# Connectors.net
KiCad netlist of a schematic drawn in Altium Designer
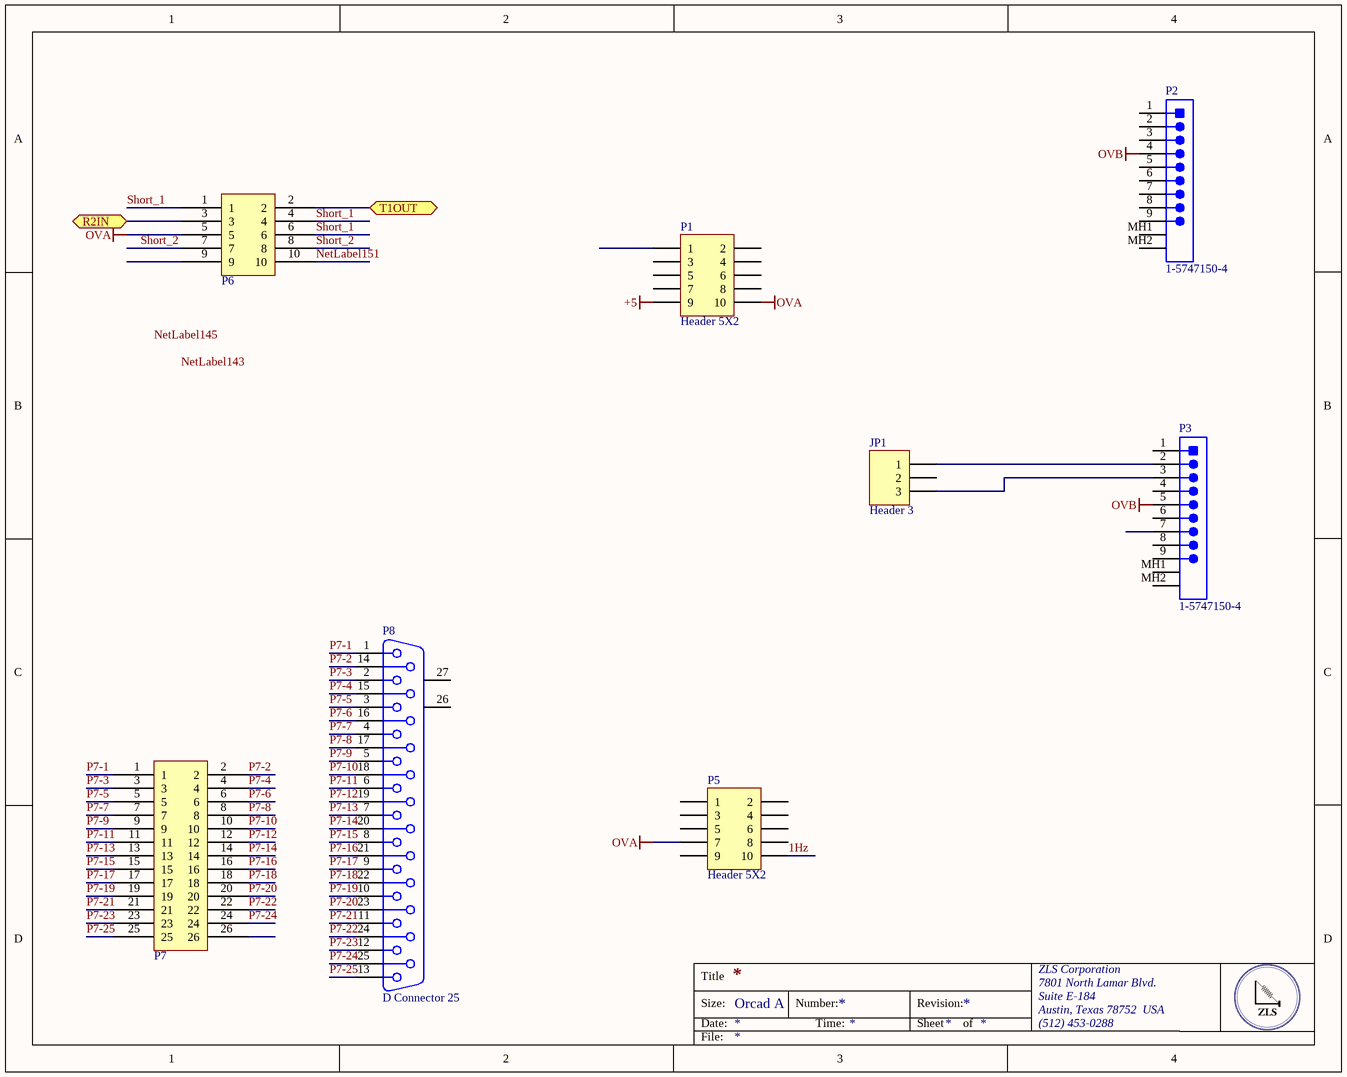
[diagram p0: Connectors.SchDoc]

(export (version "E")
  (design (tool "Eeschema 10.0.6"))
  (components
    (comp (ref "JP1")
      (value "Header 3")
      (footprint "HDR1X3")
      (description "Header, 3-Pin")
      (fields (field (name "PUBLISHER") "Altium Limited"))
      (libsource (lib "Miscellaneous Connectors") (part "Header 3"))
    )
    (comp (ref "P1")
      (value "Header 5X2")
      (footprint "HDR2X5")
      (description "Header, 5-Pin, Dual row")
      (fields (field (name "PUBLISHER") "Altium Limited"))
      (libsource (lib "Miscellaneous Connectors") (part "Header 5X2"))
    )
    (comp (ref "P2")
      (value "1-5747150-4")
      (footprint "TECO-1-5747150-4_V")
      (fields (field (name "MANUFACTURER") "TE Connectivity"))
      (libsource (lib "Altium Content Vault") (part "CMP-2000-05406-1"))
    )
    (comp (ref "P3")
      (value "1-5747150-4")
      (footprint "TECO-1-5747150-4_V")
      (fields (field (name "MANUFACTURER") "TE Connectivity"))
      (libsource (lib "Altium Content Vault") (part "CMP-2000-05406-1"))
    )
    (comp (ref "P5")
      (value "Header 5X2")
      (footprint "HDR2X5")
      (description "Header, 5-Pin, Dual row")
      (fields (field (name "PUBLISHER") "Altium Limited"))
      (libsource (lib "Miscellaneous Connectors") (part "Header 5X2"))
    )
    (comp (ref "P6")
      (value "STMM-105-01-G-D")
      (footprint "STMM-105-01-G-D")
      (fields
        (field (name "MANUFACTURER") "SAMTEC")
        (field (name "COMPONENTLINK1URL") "https://webassistants.partcommunity.com/23d-libs/samtec/search/resolve.html?EMAIL=mysamtec@samtec.com&PN=HTSW-114-05-F-D")
        (field (name "COMPONENTLINK1DESCRIPTION") "https://webassistants.partcommunity.com/23d-libs/samtec/search/resolve.html?EMAIL=mysamtec@samtec.com&PN=HTSW-114-05-F-D")
      )
      (libsource (lib "ZLS_Schematic_lib") (part "STMM-105-01-G-D"))
    )
    (comp (ref "P7")
      (value "2.00 mm Shrouded Terminal Strip, Cable Mate")
      (footprint "STMM-113-01-G-D")
      (libsource (lib "ZLS_Schematic_lib") (part "STMM-113-01-G-D"))
    )
    (comp (ref "P8")
      (value "D Connector 25")
      (footprint "DSUB1.385-2H25A")
      (description "Receptacle Assembly, 25 Position, Right Angle")
      (fields (field (name "PUBLISHER") "Altium Limited"))
      (libsource (lib "Miscellaneous Connectors") (part "D Connector 25"))
    )
  )
  (nets
    (net (code "1") (name "+5") (class "Default")
      (node (ref "P1") (pin "9") (pinfunction "9_9") (pintype "passive"))
    )
    (net (code "2") (name "/1Hz") (class "Default")
      (node (ref "P5") (pin "10") (pinfunction "10_10") (pintype "passive"))
    )
    (net (code "5") (name "/NetLabel151") (class "Default")
      (node (ref "P6") (pin "10") (pinfunction "10_10") (pintype "passive"))
    )
    (net (code "6") (name "/P7-1") (class "Default")
      (node (ref "P7") (pin "1") (pinfunction "1_1") (pintype "passive"))
      (node (ref "P8") (pin "1") (pinfunction "1_1") (pintype "passive"))
    )
    (net (code "7") (name "/P7-2") (class "Default")
      (node (ref "P7") (pin "2") (pinfunction "2_2") (pintype "passive"))
      (node (ref "P8") (pin "14") (pinfunction "14_14") (pintype "passive"))
    )
    (net (code "8") (name "/P7-3") (class "Default")
      (node (ref "P7") (pin "3") (pinfunction "3_3") (pintype "passive"))
      (node (ref "P8") (pin "2") (pinfunction "2_2") (pintype "passive"))
    )
    (net (code "9") (name "/P7-4") (class "Default")
      (node (ref "P7") (pin "4") (pinfunction "4_4") (pintype "passive"))
      (node (ref "P8") (pin "15") (pinfunction "15_15") (pintype "passive"))
    )
    (net (code "10") (name "/P7-5") (class "Default")
      (node (ref "P7") (pin "5") (pinfunction "5_5") (pintype "passive"))
      (node (ref "P8") (pin "3") (pinfunction "3_3") (pintype "passive"))
    )
    (net (code "11") (name "/P7-6") (class "Default")
      (node (ref "P7") (pin "6") (pinfunction "6_6") (pintype "passive"))
      (node (ref "P8") (pin "16") (pinfunction "16_16") (pintype "passive"))
    )
    (net (code "12") (name "/P7-7") (class "Default")
      (node (ref "P7") (pin "7") (pinfunction "7_7") (pintype "passive"))
      (node (ref "P8") (pin "4") (pinfunction "4_4") (pintype "passive"))
    )
    (net (code "13") (name "/P7-8") (class "Default")
      (node (ref "P7") (pin "8") (pinfunction "8_8") (pintype "passive"))
      (node (ref "P8") (pin "17") (pinfunction "17_17") (pintype "passive"))
    )
    (net (code "14") (name "/P7-9") (class "Default")
      (node (ref "P7") (pin "9") (pinfunction "9_9") (pintype "passive"))
      (node (ref "P8") (pin "5") (pinfunction "5_5") (pintype "passive"))
    )
    (net (code "15") (name "/P7-10") (class "Default")
      (node (ref "P7") (pin "10") (pinfunction "10_10") (pintype "passive"))
      (node (ref "P8") (pin "18") (pinfunction "18_18") (pintype "passive"))
    )
    (net (code "16") (name "/P7-11") (class "Default")
      (node (ref "P7") (pin "11") (pinfunction "11_11") (pintype "passive"))
      (node (ref "P8") (pin "6") (pinfunction "6_6") (pintype "passive"))
    )
    (net (code "17") (name "/P7-12") (class "Default")
      (node (ref "P7") (pin "12") (pinfunction "12_12") (pintype "passive"))
      (node (ref "P8") (pin "19") (pinfunction "19_19") (pintype "passive"))
    )
    (net (code "18") (name "/P7-13") (class "Default")
      (node (ref "P7") (pin "13") (pinfunction "13_13") (pintype "passive"))
      (node (ref "P8") (pin "7") (pinfunction "7_7") (pintype "passive"))
    )
    (net (code "19") (name "/P7-14") (class "Default")
      (node (ref "P7") (pin "14") (pinfunction "14_14") (pintype "passive"))
      (node (ref "P8") (pin "20") (pinfunction "20_20") (pintype "passive"))
    )
    (net (code "20") (name "/P7-15") (class "Default")
      (node (ref "P7") (pin "15") (pinfunction "15_15") (pintype "passive"))
      (node (ref "P8") (pin "8") (pinfunction "8_8") (pintype "passive"))
    )
    (net (code "21") (name "/P7-16") (class "Default")
      (node (ref "P7") (pin "16") (pinfunction "16_16") (pintype "passive"))
      (node (ref "P8") (pin "21") (pinfunction "21_21") (pintype "passive"))
    )
    (net (code "22") (name "/P7-17") (class "Default")
      (node (ref "P7") (pin "17") (pinfunction "17_17") (pintype "passive"))
      (node (ref "P8") (pin "9") (pinfunction "9_9") (pintype "passive"))
    )
    (net (code "23") (name "/P7-18") (class "Default")
      (node (ref "P7") (pin "18") (pinfunction "18_18") (pintype "passive"))
      (node (ref "P8") (pin "22") (pinfunction "22_22") (pintype "passive"))
    )
    (net (code "24") (name "/P7-19") (class "Default")
      (node (ref "P7") (pin "19") (pinfunction "19_19") (pintype "passive"))
      (node (ref "P8") (pin "10") (pinfunction "10_10") (pintype "passive"))
    )
    (net (code "25") (name "/P7-20") (class "Default")
      (node (ref "P7") (pin "20") (pinfunction "20_20") (pintype "passive"))
      (node (ref "P8") (pin "23") (pinfunction "23_23") (pintype "passive"))
    )
    (net (code "26") (name "/P7-21") (class "Default")
      (node (ref "P7") (pin "21") (pinfunction "21_21") (pintype "passive"))
      (node (ref "P8") (pin "11") (pinfunction "11_11") (pintype "passive"))
    )
    (net (code "27") (name "/P7-22") (class "Default")
      (node (ref "P7") (pin "22") (pinfunction "22_22") (pintype "passive"))
      (node (ref "P8") (pin "24") (pinfunction "24_24") (pintype "passive"))
    )
    (net (code "28") (name "/P7-23") (class "Default")
      (node (ref "P7") (pin "23") (pinfunction "23_23") (pintype "passive"))
      (node (ref "P8") (pin "12") (pinfunction "12_12") (pintype "passive"))
    )
    (net (code "29") (name "/P7-24") (class "Default")
      (node (ref "P7") (pin "24") (pinfunction "24_24") (pintype "passive"))
      (node (ref "P8") (pin "25") (pinfunction "25_25") (pintype "passive"))
    )
    (net (code "30") (name "/P7-25") (class "Default")
      (node (ref "P7") (pin "25") (pinfunction "25_25") (pintype "passive"))
      (node (ref "P8") (pin "13") (pinfunction "13_13") (pintype "passive"))
    )
    (net (code "31") (name "/R2IN") (class "Default")
      (node (ref "P6") (pin "3") (pinfunction "3_3") (pintype "passive"))
    )
    (net (code "32") (name "/Short_1") (class "Default")
      (node (ref "P6") (pin "1") (pinfunction "1_1") (pintype "passive"))
      (node (ref "P6") (pin "4") (pinfunction "4_4") (pintype "passive"))
      (node (ref "P6") (pin "6") (pinfunction "6_6") (pintype "passive"))
    )
    (net (code "33") (name "/Short_2") (class "Default")
      (node (ref "P6") (pin "7") (pinfunction "7_7") (pintype "passive"))
      (node (ref "P6") (pin "8") (pinfunction "8_8") (pintype "passive"))
    )
    (net (code "34") (name "/T1OUT") (class "Default")
      (node (ref "P6") (pin "2") (pinfunction "2_2") (pintype "passive"))
    )
    (net (code "35") (name "Net-(JP1-Pad1)") (class "Default")
      (node (ref "JP1") (pin "1") (pinfunction "1_1") (pintype "passive"))
      (node (ref "P3") (pin "2") (pinfunction "2_2") (pintype "passive"))
    )
    (net (code "36") (name "Net-(JP1-Pad3)") (class "Default")
      (node (ref "JP1") (pin "3") (pinfunction "3_3") (pintype "passive"))
      (node (ref "P3") (pin "3") (pinfunction "3_3") (pintype "passive"))
    )
    (net (code "37") (name "OVA") (class "Default")
      (node (ref "P1") (pin "10") (pinfunction "10_10") (pintype "passive"))
      (node (ref "P5") (pin "7") (pinfunction "7_7") (pintype "passive"))
      (node (ref "P6") (pin "5") (pinfunction "5_5") (pintype "passive"))
    )
    (net (code "38") (name "OVB") (class "Default")
      (node (ref "P2") (pin "4") (pinfunction "4_4") (pintype "passive"))
      (node (ref "P3") (pin "5") (pinfunction "5_5") (pintype "passive"))
    )
    (net (code "39") (name "unconnected-(JP1-Pad2)") (class "Default")
      (node (ref "JP1") (pin "2") (pinfunction "2_2") (pintype "passive"))
    )
    (net (code "40") (name "unconnected-(P1-Pad1)") (class "Default")
      (node (ref "P1") (pin "1") (pinfunction "1_1") (pintype "passive"))
    )
    (net (code "41") (name "unconnected-(P1-Pad2)") (class "Default")
      (node (ref "P1") (pin "2") (pinfunction "2_2") (pintype "passive"))
    )
    (net (code "42") (name "unconnected-(P1-Pad3)") (class "Default")
      (node (ref "P1") (pin "3") (pinfunction "3_3") (pintype "passive"))
    )
    (net (code "43") (name "unconnected-(P1-Pad4)") (class "Default")
      (node (ref "P1") (pin "4") (pinfunction "4_4") (pintype "passive"))
    )
    (net (code "44") (name "unconnected-(P1-Pad5)") (class "Default")
      (node (ref "P1") (pin "5") (pinfunction "5_5") (pintype "passive"))
    )
    (net (code "45") (name "unconnected-(P1-Pad6)") (class "Default")
      (node (ref "P1") (pin "6") (pinfunction "6_6") (pintype "passive"))
    )
    (net (code "46") (name "unconnected-(P1-Pad7)") (class "Default")
      (node (ref "P1") (pin "7") (pinfunction "7_7") (pintype "passive"))
    )
    (net (code "47") (name "unconnected-(P1-Pad8)") (class "Default")
      (node (ref "P1") (pin "8") (pinfunction "8_8") (pintype "passive"))
    )
    (net (code "48") (name "unconnected-(P2-Pad1)") (class "Default")
      (node (ref "P2") (pin "1") (pinfunction "1_1") (pintype "passive"))
    )
    (net (code "49") (name "unconnected-(P2-Pad2)") (class "Default")
      (node (ref "P2") (pin "2") (pinfunction "2_2") (pintype "passive"))
    )
    (net (code "50") (name "unconnected-(P2-Pad3)") (class "Default")
      (node (ref "P2") (pin "3") (pinfunction "3_3") (pintype "passive"))
    )
    (net (code "51") (name "unconnected-(P2-Pad5)") (class "Default")
      (node (ref "P2") (pin "5") (pinfunction "5_5") (pintype "passive"))
    )
    (net (code "52") (name "unconnected-(P2-Pad6)") (class "Default")
      (node (ref "P2") (pin "6") (pinfunction "6_6") (pintype "passive"))
    )
    (net (code "53") (name "unconnected-(P2-Pad7)") (class "Default")
      (node (ref "P2") (pin "7") (pinfunction "7_7") (pintype "passive"))
    )
    (net (code "54") (name "unconnected-(P2-Pad8)") (class "Default")
      (node (ref "P2") (pin "8") (pinfunction "8_8") (pintype "passive"))
    )
    (net (code "55") (name "unconnected-(P2-Pad9)") (class "Default")
      (node (ref "P2") (pin "9") (pinfunction "9_9") (pintype "passive"))
    )
    (net (code "56") (name "unconnected-(P2-PadMH1)") (class "Default")
      (node (ref "P2") (pin "MH1") (pinfunction "MH1_MH1") (pintype "passive"))
    )
    (net (code "57") (name "unconnected-(P2-PadMH2)") (class "Default")
      (node (ref "P2") (pin "MH2") (pinfunction "MH2_MH2") (pintype "passive"))
    )
    (net (code "58") (name "unconnected-(P3-Pad1)") (class "Default")
      (node (ref "P3") (pin "1") (pinfunction "1_1") (pintype "passive"))
    )
    (net (code "59") (name "unconnected-(P3-Pad4)") (class "Default")
      (node (ref "P3") (pin "4") (pinfunction "4_4") (pintype "passive"))
    )
    (net (code "60") (name "unconnected-(P3-Pad6)") (class "Default")
      (node (ref "P3") (pin "6") (pinfunction "6_6") (pintype "passive"))
    )
    (net (code "61") (name "unconnected-(P3-Pad7)") (class "Default")
      (node (ref "P3") (pin "7") (pinfunction "7_7") (pintype "passive"))
    )
    (net (code "62") (name "unconnected-(P3-Pad8)") (class "Default")
      (node (ref "P3") (pin "8") (pinfunction "8_8") (pintype "passive"))
    )
    (net (code "63") (name "unconnected-(P3-Pad9)") (class "Default")
      (node (ref "P3") (pin "9") (pinfunction "9_9") (pintype "passive"))
    )
    (net (code "64") (name "unconnected-(P3-PadMH1)") (class "Default")
      (node (ref "P3") (pin "MH1") (pinfunction "MH1_MH1") (pintype "passive"))
    )
    (net (code "65") (name "unconnected-(P3-PadMH2)") (class "Default")
      (node (ref "P3") (pin "MH2") (pinfunction "MH2_MH2") (pintype "passive"))
    )
    (net (code "66") (name "unconnected-(P5-Pad1)") (class "Default")
      (node (ref "P5") (pin "1") (pinfunction "1_1") (pintype "passive"))
    )
    (net (code "67") (name "unconnected-(P5-Pad2)") (class "Default")
      (node (ref "P5") (pin "2") (pinfunction "2_2") (pintype "passive"))
    )
    (net (code "68") (name "unconnected-(P5-Pad3)") (class "Default")
      (node (ref "P5") (pin "3") (pinfunction "3_3") (pintype "passive"))
    )
    (net (code "69") (name "unconnected-(P5-Pad4)") (class "Default")
      (node (ref "P5") (pin "4") (pinfunction "4_4") (pintype "passive"))
    )
    (net (code "70") (name "unconnected-(P5-Pad5)") (class "Default")
      (node (ref "P5") (pin "5") (pinfunction "5_5") (pintype "passive"))
    )
    (net (code "71") (name "unconnected-(P5-Pad6)") (class "Default")
      (node (ref "P5") (pin "6") (pinfunction "6_6") (pintype "passive"))
    )
    (net (code "72") (name "unconnected-(P5-Pad8)") (class "Default")
      (node (ref "P5") (pin "8") (pinfunction "8_8") (pintype "passive"))
    )
    (net (code "73") (name "unconnected-(P5-Pad9)") (class "Default")
      (node (ref "P5") (pin "9") (pinfunction "9_9") (pintype "passive"))
    )
    (net (code "74") (name "unconnected-(P6-Pad9)") (class "Default")
      (node (ref "P6") (pin "9") (pinfunction "9_9") (pintype "passive"))
    )
    (net (code "75") (name "unconnected-(P7-Pad26)") (class "Default")
      (node (ref "P7") (pin "26") (pinfunction "26_26") (pintype "passive"))
    )
    (net (code "76") (name "unconnected-(P8-MH1-Pad26)") (class "Default")
      (node (ref "P8") (pin "26") (pinfunction "MH1_26") (pintype "passive"))
    )
    (net (code "77") (name "unconnected-(P8-MH2-Pad27)") (class "Default")
      (node (ref "P8") (pin "27") (pinfunction "MH2_27") (pintype "passive"))
    )
  )
)
